# Audio-Beamformer_LED_V1_0.net
KiCad netlist of a schematic drawn in Altium Designer
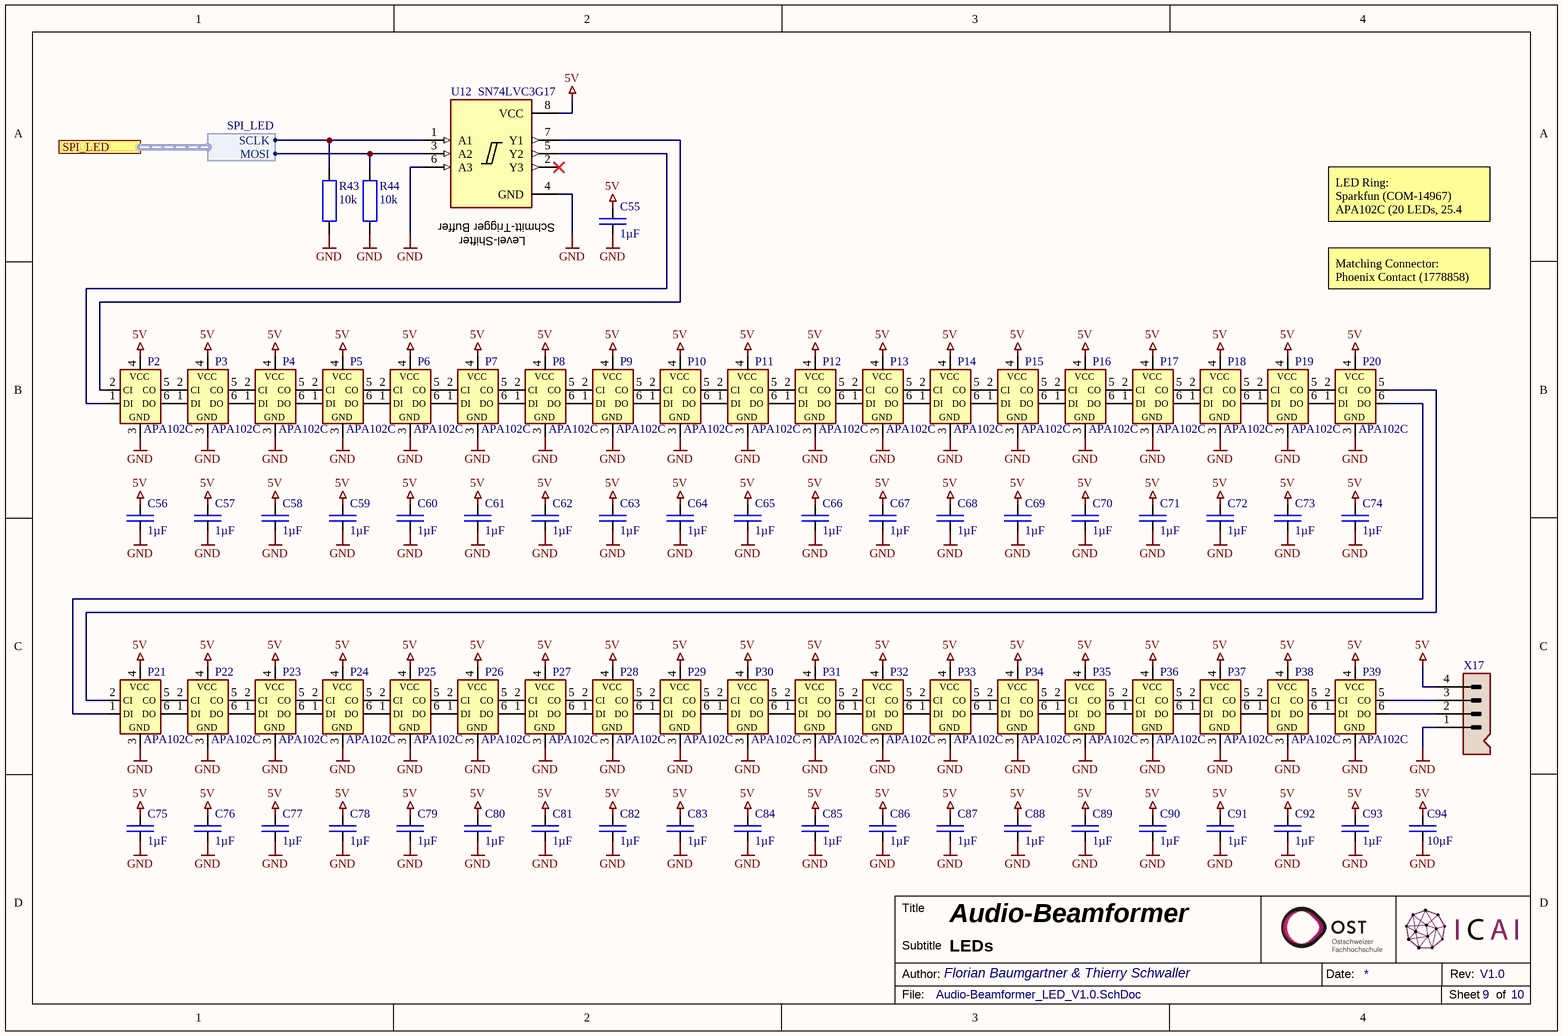
[diagram p0: Audio-Beamformer_LED_V1.0.SchDoc]

(export (version "E")
  (design (tool "Eeschema 10.0.6"))
  (components
    (comp (ref "C55")
      (value "1µF")
      (footprint "SMD Keramikkondensator 0603")
      (description "CAP-MK")
      (libsource (lib "AudioAmp") (part "C-CAPACITOR"))
    )
    (comp (ref "C56")
      (value "1µF")
      (footprint "SMD Keramikkondensator 0603")
      (description "CAP-MK")
      (libsource (lib "AudioAmp") (part "C-CAPACITOR"))
    )
    (comp (ref "C57")
      (value "1µF")
      (footprint "SMD Keramikkondensator 0603")
      (description "CAP-MK")
      (libsource (lib "AudioAmp") (part "C-CAPACITOR"))
    )
    (comp (ref "C58")
      (value "1µF")
      (footprint "SMD Keramikkondensator 0603")
      (description "CAP-MK")
      (libsource (lib "AudioAmp") (part "C-CAPACITOR"))
    )
    (comp (ref "C59")
      (value "1µF")
      (footprint "SMD Keramikkondensator 0603")
      (description "CAP-MK")
      (libsource (lib "AudioAmp") (part "C-CAPACITOR"))
    )
    (comp (ref "C60")
      (value "1µF")
      (footprint "SMD Keramikkondensator 0603")
      (description "CAP-MK")
      (libsource (lib "AudioAmp") (part "C-CAPACITOR"))
    )
    (comp (ref "C61")
      (value "1µF")
      (footprint "SMD Keramikkondensator 0603")
      (description "CAP-MK")
      (libsource (lib "AudioAmp") (part "C-CAPACITOR"))
    )
    (comp (ref "C62")
      (value "1µF")
      (footprint "SMD Keramikkondensator 0603")
      (description "CAP-MK")
      (libsource (lib "AudioAmp") (part "C-CAPACITOR"))
    )
    (comp (ref "C63")
      (value "1µF")
      (footprint "SMD Keramikkondensator 0603")
      (description "CAP-MK")
      (libsource (lib "AudioAmp") (part "C-CAPACITOR"))
    )
    (comp (ref "C64")
      (value "1µF")
      (footprint "SMD Keramikkondensator 0603")
      (description "CAP-MK")
      (libsource (lib "AudioAmp") (part "C-CAPACITOR"))
    )
    (comp (ref "C65")
      (value "1µF")
      (footprint "SMD Keramikkondensator 0603")
      (description "CAP-MK")
      (libsource (lib "AudioAmp") (part "C-CAPACITOR"))
    )
    (comp (ref "C66")
      (value "1µF")
      (footprint "SMD Keramikkondensator 0603")
      (description "CAP-MK")
      (libsource (lib "AudioAmp") (part "C-CAPACITOR"))
    )
    (comp (ref "C67")
      (value "1µF")
      (footprint "SMD Keramikkondensator 0603")
      (description "CAP-MK")
      (libsource (lib "AudioAmp") (part "C-CAPACITOR"))
    )
    (comp (ref "C68")
      (value "1µF")
      (footprint "SMD Keramikkondensator 0603")
      (description "CAP-MK")
      (libsource (lib "AudioAmp") (part "C-CAPACITOR"))
    )
    (comp (ref "C69")
      (value "1µF")
      (footprint "SMD Keramikkondensator 0603")
      (description "CAP-MK")
      (libsource (lib "AudioAmp") (part "C-CAPACITOR"))
    )
    (comp (ref "C70")
      (value "1µF")
      (footprint "SMD Keramikkondensator 0603")
      (description "CAP-MK")
      (libsource (lib "AudioAmp") (part "C-CAPACITOR"))
    )
    (comp (ref "C71")
      (value "1µF")
      (footprint "SMD Keramikkondensator 0603")
      (description "CAP-MK")
      (libsource (lib "AudioAmp") (part "C-CAPACITOR"))
    )
    (comp (ref "C72")
      (value "1µF")
      (footprint "SMD Keramikkondensator 0603")
      (description "CAP-MK")
      (libsource (lib "AudioAmp") (part "C-CAPACITOR"))
    )
    (comp (ref "C73")
      (value "1µF")
      (footprint "SMD Keramikkondensator 0603")
      (description "CAP-MK")
      (libsource (lib "AudioAmp") (part "C-CAPACITOR"))
    )
    (comp (ref "C74")
      (value "1µF")
      (footprint "SMD Keramikkondensator 0603")
      (description "CAP-MK")
      (libsource (lib "AudioAmp") (part "C-CAPACITOR"))
    )
    (comp (ref "C75")
      (value "1µF")
      (footprint "SMD Keramikkondensator 0603")
      (description "CAP-MK")
      (libsource (lib "AudioAmp") (part "C-CAPACITOR"))
    )
    (comp (ref "C76")
      (value "1µF")
      (footprint "SMD Keramikkondensator 0603")
      (description "CAP-MK")
      (libsource (lib "AudioAmp") (part "C-CAPACITOR"))
    )
    (comp (ref "C77")
      (value "1µF")
      (footprint "SMD Keramikkondensator 0603")
      (description "CAP-MK")
      (libsource (lib "AudioAmp") (part "C-CAPACITOR"))
    )
    (comp (ref "C78")
      (value "1µF")
      (footprint "SMD Keramikkondensator 0603")
      (description "CAP-MK")
      (libsource (lib "AudioAmp") (part "C-CAPACITOR"))
    )
    (comp (ref "C79")
      (value "1µF")
      (footprint "SMD Keramikkondensator 0603")
      (description "CAP-MK")
      (libsource (lib "AudioAmp") (part "C-CAPACITOR"))
    )
    (comp (ref "C80")
      (value "1µF")
      (footprint "SMD Keramikkondensator 0603")
      (description "CAP-MK")
      (libsource (lib "AudioAmp") (part "C-CAPACITOR"))
    )
    (comp (ref "C81")
      (value "1µF")
      (footprint "SMD Keramikkondensator 0603")
      (description "CAP-MK")
      (libsource (lib "AudioAmp") (part "C-CAPACITOR"))
    )
    (comp (ref "C82")
      (value "1µF")
      (footprint "SMD Keramikkondensator 0603")
      (description "CAP-MK")
      (libsource (lib "AudioAmp") (part "C-CAPACITOR"))
    )
    (comp (ref "C83")
      (value "1µF")
      (footprint "SMD Keramikkondensator 0603")
      (description "CAP-MK")
      (libsource (lib "AudioAmp") (part "C-CAPACITOR"))
    )
    (comp (ref "C84")
      (value "1µF")
      (footprint "SMD Keramikkondensator 0603")
      (description "CAP-MK")
      (libsource (lib "AudioAmp") (part "C-CAPACITOR"))
    )
    (comp (ref "C85")
      (value "1µF")
      (footprint "SMD Keramikkondensator 0603")
      (description "CAP-MK")
      (libsource (lib "AudioAmp") (part "C-CAPACITOR"))
    )
    (comp (ref "C86")
      (value "1µF")
      (footprint "SMD Keramikkondensator 0603")
      (description "CAP-MK")
      (libsource (lib "AudioAmp") (part "C-CAPACITOR"))
    )
    (comp (ref "C87")
      (value "1µF")
      (footprint "SMD Keramikkondensator 0603")
      (description "CAP-MK")
      (libsource (lib "AudioAmp") (part "C-CAPACITOR"))
    )
    (comp (ref "C88")
      (value "1µF")
      (footprint "SMD Keramikkondensator 0603")
      (description "CAP-MK")
      (libsource (lib "AudioAmp") (part "C-CAPACITOR"))
    )
    (comp (ref "C89")
      (value "1µF")
      (footprint "SMD Keramikkondensator 0603")
      (description "CAP-MK")
      (libsource (lib "AudioAmp") (part "C-CAPACITOR"))
    )
    (comp (ref "C90")
      (value "1µF")
      (footprint "SMD Keramikkondensator 0603")
      (description "CAP-MK")
      (libsource (lib "AudioAmp") (part "C-CAPACITOR"))
    )
    (comp (ref "C91")
      (value "1µF")
      (footprint "SMD Keramikkondensator 0603")
      (description "CAP-MK")
      (libsource (lib "AudioAmp") (part "C-CAPACITOR"))
    )
    (comp (ref "C92")
      (value "1µF")
      (footprint "SMD Keramikkondensator 0603")
      (description "CAP-MK")
      (libsource (lib "AudioAmp") (part "C-CAPACITOR"))
    )
    (comp (ref "C93")
      (value "1µF")
      (footprint "SMD Keramikkondensator 0603")
      (description "CAP-MK")
      (libsource (lib "AudioAmp") (part "C-CAPACITOR"))
    )
    (comp (ref "C94")
      (value "10µF")
      (footprint "SMD Keramikkondensator 1206")
      (description "CAP-MK")
      (libsource (lib "AudioAmp") (part "C-CAPACITOR"))
    )
    (comp (ref "P2")
      (value "APA102C")
      (footprint "SMD LED APA102C-5050")
      (description "Smart RGB-LED")
      (libsource (lib "Audio-Beamformer") (part "P-APA102C"))
    )
    (comp (ref "P3")
      (value "APA102C")
      (footprint "SMD LED APA102C-5050")
      (description "Smart RGB-LED")
      (libsource (lib "Audio-Beamformer") (part "P-APA102C"))
    )
    (comp (ref "P4")
      (value "APA102C")
      (footprint "SMD LED APA102C-5050")
      (description "Smart RGB-LED")
      (libsource (lib "Audio-Beamformer") (part "P-APA102C"))
    )
    (comp (ref "P5")
      (value "APA102C")
      (footprint "SMD LED APA102C-5050")
      (description "Smart RGB-LED")
      (libsource (lib "Audio-Beamformer") (part "P-APA102C"))
    )
    (comp (ref "P6")
      (value "APA102C")
      (footprint "SMD LED APA102C-5050")
      (description "Smart RGB-LED")
      (libsource (lib "Audio-Beamformer") (part "P-APA102C"))
    )
    (comp (ref "P7")
      (value "APA102C")
      (footprint "SMD LED APA102C-5050")
      (description "Smart RGB-LED")
      (libsource (lib "Audio-Beamformer") (part "P-APA102C"))
    )
    (comp (ref "P8")
      (value "APA102C")
      (footprint "SMD LED APA102C-5050")
      (description "Smart RGB-LED")
      (libsource (lib "Audio-Beamformer") (part "P-APA102C"))
    )
    (comp (ref "P9")
      (value "APA102C")
      (footprint "SMD LED APA102C-5050")
      (description "Smart RGB-LED")
      (libsource (lib "Audio-Beamformer") (part "P-APA102C"))
    )
    (comp (ref "P10")
      (value "APA102C")
      (footprint "SMD LED APA102C-5050")
      (description "Smart RGB-LED")
      (libsource (lib "Audio-Beamformer") (part "P-APA102C"))
    )
    (comp (ref "P11")
      (value "APA102C")
      (footprint "SMD LED APA102C-5050")
      (description "Smart RGB-LED")
      (libsource (lib "Audio-Beamformer") (part "P-APA102C"))
    )
    (comp (ref "P12")
      (value "APA102C")
      (footprint "SMD LED APA102C-5050")
      (description "Smart RGB-LED")
      (libsource (lib "Audio-Beamformer") (part "P-APA102C"))
    )
    (comp (ref "P13")
      (value "APA102C")
      (footprint "SMD LED APA102C-5050")
      (description "Smart RGB-LED")
      (libsource (lib "Audio-Beamformer") (part "P-APA102C"))
    )
    (comp (ref "P14")
      (value "APA102C")
      (footprint "SMD LED APA102C-5050")
      (description "Smart RGB-LED")
      (libsource (lib "Audio-Beamformer") (part "P-APA102C"))
    )
    (comp (ref "P15")
      (value "APA102C")
      (footprint "SMD LED APA102C-5050")
      (description "Smart RGB-LED")
      (libsource (lib "Audio-Beamformer") (part "P-APA102C"))
    )
    (comp (ref "P16")
      (value "APA102C")
      (footprint "SMD LED APA102C-5050")
      (description "Smart RGB-LED")
      (libsource (lib "Audio-Beamformer") (part "P-APA102C"))
    )
    (comp (ref "P17")
      (value "APA102C")
      (footprint "SMD LED APA102C-5050")
      (description "Smart RGB-LED")
      (libsource (lib "Audio-Beamformer") (part "P-APA102C"))
    )
    (comp (ref "P18")
      (value "APA102C")
      (footprint "SMD LED APA102C-5050")
      (description "Smart RGB-LED")
      (libsource (lib "Audio-Beamformer") (part "P-APA102C"))
    )
    (comp (ref "P19")
      (value "APA102C")
      (footprint "SMD LED APA102C-5050")
      (description "Smart RGB-LED")
      (libsource (lib "Audio-Beamformer") (part "P-APA102C"))
    )
    (comp (ref "P20")
      (value "APA102C")
      (footprint "SMD LED APA102C-5050")
      (description "Smart RGB-LED")
      (libsource (lib "Audio-Beamformer") (part "P-APA102C"))
    )
    (comp (ref "P21")
      (value "APA102C")
      (footprint "SMD LED APA102C-5050")
      (description "Smart RGB-LED")
      (libsource (lib "Audio-Beamformer") (part "P-APA102C"))
    )
    (comp (ref "P22")
      (value "APA102C")
      (footprint "SMD LED APA102C-5050")
      (description "Smart RGB-LED")
      (libsource (lib "Audio-Beamformer") (part "P-APA102C"))
    )
    (comp (ref "P23")
      (value "APA102C")
      (footprint "SMD LED APA102C-5050")
      (description "Smart RGB-LED")
      (libsource (lib "Audio-Beamformer") (part "P-APA102C"))
    )
    (comp (ref "P24")
      (value "APA102C")
      (footprint "SMD LED APA102C-5050")
      (description "Smart RGB-LED")
      (libsource (lib "Audio-Beamformer") (part "P-APA102C"))
    )
    (comp (ref "P25")
      (value "APA102C")
      (footprint "SMD LED APA102C-5050")
      (description "Smart RGB-LED")
      (libsource (lib "Audio-Beamformer") (part "P-APA102C"))
    )
    (comp (ref "P26")
      (value "APA102C")
      (footprint "SMD LED APA102C-5050")
      (description "Smart RGB-LED")
      (libsource (lib "Audio-Beamformer") (part "P-APA102C"))
    )
    (comp (ref "P27")
      (value "APA102C")
      (footprint "SMD LED APA102C-5050")
      (description "Smart RGB-LED")
      (libsource (lib "Audio-Beamformer") (part "P-APA102C"))
    )
    (comp (ref "P28")
      (value "APA102C")
      (footprint "SMD LED APA102C-5050")
      (description "Smart RGB-LED")
      (libsource (lib "Audio-Beamformer") (part "P-APA102C"))
    )
    (comp (ref "P29")
      (value "APA102C")
      (footprint "SMD LED APA102C-5050")
      (description "Smart RGB-LED")
      (libsource (lib "Audio-Beamformer") (part "P-APA102C"))
    )
    (comp (ref "P30")
      (value "APA102C")
      (footprint "SMD LED APA102C-5050")
      (description "Smart RGB-LED")
      (libsource (lib "Audio-Beamformer") (part "P-APA102C"))
    )
    (comp (ref "P31")
      (value "APA102C")
      (footprint "SMD LED APA102C-5050")
      (description "Smart RGB-LED")
      (libsource (lib "Audio-Beamformer") (part "P-APA102C"))
    )
    (comp (ref "P32")
      (value "APA102C")
      (footprint "SMD LED APA102C-5050")
      (description "Smart RGB-LED")
      (libsource (lib "Audio-Beamformer") (part "P-APA102C"))
    )
    (comp (ref "P33")
      (value "APA102C")
      (footprint "SMD LED APA102C-5050")
      (description "Smart RGB-LED")
      (libsource (lib "Audio-Beamformer") (part "P-APA102C"))
    )
    (comp (ref "P34")
      (value "APA102C")
      (footprint "SMD LED APA102C-5050")
      (description "Smart RGB-LED")
      (libsource (lib "Audio-Beamformer") (part "P-APA102C"))
    )
    (comp (ref "P35")
      (value "APA102C")
      (footprint "SMD LED APA102C-5050")
      (description "Smart RGB-LED")
      (libsource (lib "Audio-Beamformer") (part "P-APA102C"))
    )
    (comp (ref "P36")
      (value "APA102C")
      (footprint "SMD LED APA102C-5050")
      (description "Smart RGB-LED")
      (libsource (lib "Audio-Beamformer") (part "P-APA102C"))
    )
    (comp (ref "P37")
      (value "APA102C")
      (footprint "SMD LED APA102C-5050")
      (description "Smart RGB-LED")
      (libsource (lib "Audio-Beamformer") (part "P-APA102C"))
    )
    (comp (ref "P38")
      (value "APA102C")
      (footprint "SMD LED APA102C-5050")
      (description "Smart RGB-LED")
      (libsource (lib "Audio-Beamformer") (part "P-APA102C"))
    )
    (comp (ref "P39")
      (value "APA102C")
      (footprint "SMD LED APA102C-5050")
      (description "Smart RGB-LED")
      (libsource (lib "Audio-Beamformer") (part "P-APA102C"))
    )
    (comp (ref "R43")
      (value "10k")
      (footprint "SMD Widerstand 0603")
      (description "RES (E=Heizwiderstand B=Messwandler)")
      (libsource (lib "TFS Integrated Library") (part "R-RESISTOR"))
    )
    (comp (ref "R44")
      (value "10k")
      (footprint "SMD Widerstand 0603")
      (description "RES (E=Heizwiderstand B=Messwandler)")
      (libsource (lib "TFS Integrated Library") (part "R-RESISTOR"))
    )
    (comp (ref "U12")
      (value "SN74LVC3G17")
      (footprint "SMD IC SM-8")
      (description "Tripple Schmitt-Trigger Buffer")
      (libsource (lib "Audio-Beamformer") (part "U-SN74LVC3G17DCTR"))
    )
    (comp (ref "X17")
      (value "Board-To-Wire Connector (Receptacle)")
      (footprint "THT Connector 2.5mm 4-Pol (1778641)")
      (libsource (lib "Audio-Beamformer") (part "X-Stiftleiste (4-Fach)"))
    )
  )
  (nets
    (net (code "3") (name "5V") (class "Default")
      (node (ref "C55") (pin "2") (pinfunction "2_2") (pintype "passive"))
      (node (ref "C56") (pin "2") (pinfunction "2_2") (pintype "passive"))
      (node (ref "C57") (pin "2") (pinfunction "2_2") (pintype "passive"))
      (node (ref "C58") (pin "2") (pinfunction "2_2") (pintype "passive"))
      (node (ref "C59") (pin "2") (pinfunction "2_2") (pintype "passive"))
      (node (ref "C60") (pin "2") (pinfunction "2_2") (pintype "passive"))
      (node (ref "C61") (pin "2") (pinfunction "2_2") (pintype "passive"))
      (node (ref "C62") (pin "2") (pinfunction "2_2") (pintype "passive"))
      (node (ref "C63") (pin "2") (pinfunction "2_2") (pintype "passive"))
      (node (ref "C64") (pin "2") (pinfunction "2_2") (pintype "passive"))
      (node (ref "C65") (pin "2") (pinfunction "2_2") (pintype "passive"))
      (node (ref "C66") (pin "2") (pinfunction "2_2") (pintype "passive"))
      (node (ref "C67") (pin "2") (pinfunction "2_2") (pintype "passive"))
      (node (ref "C68") (pin "2") (pinfunction "2_2") (pintype "passive"))
      (node (ref "C69") (pin "2") (pinfunction "2_2") (pintype "passive"))
      (node (ref "C70") (pin "2") (pinfunction "2_2") (pintype "passive"))
      (node (ref "C71") (pin "2") (pinfunction "2_2") (pintype "passive"))
      (node (ref "C72") (pin "2") (pinfunction "2_2") (pintype "passive"))
      (node (ref "C73") (pin "2") (pinfunction "2_2") (pintype "passive"))
      (node (ref "C74") (pin "2") (pinfunction "2_2") (pintype "passive"))
      (node (ref "C75") (pin "2") (pinfunction "2_2") (pintype "passive"))
      (node (ref "C76") (pin "2") (pinfunction "2_2") (pintype "passive"))
      (node (ref "C77") (pin "2") (pinfunction "2_2") (pintype "passive"))
      (node (ref "C78") (pin "2") (pinfunction "2_2") (pintype "passive"))
      (node (ref "C79") (pin "2") (pinfunction "2_2") (pintype "passive"))
      (node (ref "C80") (pin "2") (pinfunction "2_2") (pintype "passive"))
      (node (ref "C81") (pin "2") (pinfunction "2_2") (pintype "passive"))
      (node (ref "C82") (pin "2") (pinfunction "2_2") (pintype "passive"))
      (node (ref "C83") (pin "2") (pinfunction "2_2") (pintype "passive"))
      (node (ref "C84") (pin "2") (pinfunction "2_2") (pintype "passive"))
      (node (ref "C85") (pin "2") (pinfunction "2_2") (pintype "passive"))
      (node (ref "C86") (pin "2") (pinfunction "2_2") (pintype "passive"))
      (node (ref "C87") (pin "2") (pinfunction "2_2") (pintype "passive"))
      (node (ref "C88") (pin "2") (pinfunction "2_2") (pintype "passive"))
      (node (ref "C89") (pin "2") (pinfunction "2_2") (pintype "passive"))
      (node (ref "C90") (pin "2") (pinfunction "2_2") (pintype "passive"))
      (node (ref "C91") (pin "2") (pinfunction "2_2") (pintype "passive"))
      (node (ref "C92") (pin "2") (pinfunction "2_2") (pintype "passive"))
      (node (ref "C93") (pin "2") (pinfunction "2_2") (pintype "passive"))
      (node (ref "C94") (pin "2") (pinfunction "2_2") (pintype "passive"))
      (node (ref "P10") (pin "4") (pinfunction "VCC_4") (pintype "power_in"))
      (node (ref "P11") (pin "4") (pinfunction "VCC_4") (pintype "power_in"))
      (node (ref "P12") (pin "4") (pinfunction "VCC_4") (pintype "power_in"))
      (node (ref "P13") (pin "4") (pinfunction "VCC_4") (pintype "power_in"))
      (node (ref "P14") (pin "4") (pinfunction "VCC_4") (pintype "power_in"))
      (node (ref "P15") (pin "4") (pinfunction "VCC_4") (pintype "power_in"))
      (node (ref "P16") (pin "4") (pinfunction "VCC_4") (pintype "power_in"))
      (node (ref "P17") (pin "4") (pinfunction "VCC_4") (pintype "power_in"))
      (node (ref "P18") (pin "4") (pinfunction "VCC_4") (pintype "power_in"))
      (node (ref "P19") (pin "4") (pinfunction "VCC_4") (pintype "power_in"))
      (node (ref "P2") (pin "4") (pinfunction "VCC_4") (pintype "power_in"))
      (node (ref "P20") (pin "4") (pinfunction "VCC_4") (pintype "power_in"))
      (node (ref "P21") (pin "4") (pinfunction "VCC_4") (pintype "power_in"))
      (node (ref "P22") (pin "4") (pinfunction "VCC_4") (pintype "power_in"))
      (node (ref "P23") (pin "4") (pinfunction "VCC_4") (pintype "power_in"))
      (node (ref "P24") (pin "4") (pinfunction "VCC_4") (pintype "power_in"))
      (node (ref "P25") (pin "4") (pinfunction "VCC_4") (pintype "power_in"))
      (node (ref "P26") (pin "4") (pinfunction "VCC_4") (pintype "power_in"))
      (node (ref "P27") (pin "4") (pinfunction "VCC_4") (pintype "power_in"))
      (node (ref "P28") (pin "4") (pinfunction "VCC_4") (pintype "power_in"))
      (node (ref "P29") (pin "4") (pinfunction "VCC_4") (pintype "power_in"))
      (node (ref "P3") (pin "4") (pinfunction "VCC_4") (pintype "power_in"))
      (node (ref "P30") (pin "4") (pinfunction "VCC_4") (pintype "power_in"))
      (node (ref "P31") (pin "4") (pinfunction "VCC_4") (pintype "power_in"))
      (node (ref "P32") (pin "4") (pinfunction "VCC_4") (pintype "power_in"))
      (node (ref "P33") (pin "4") (pinfunction "VCC_4") (pintype "power_in"))
      (node (ref "P34") (pin "4") (pinfunction "VCC_4") (pintype "power_in"))
      (node (ref "P35") (pin "4") (pinfunction "VCC_4") (pintype "power_in"))
      (node (ref "P36") (pin "4") (pinfunction "VCC_4") (pintype "power_in"))
      (node (ref "P37") (pin "4") (pinfunction "VCC_4") (pintype "power_in"))
      (node (ref "P38") (pin "4") (pinfunction "VCC_4") (pintype "power_in"))
      (node (ref "P39") (pin "4") (pinfunction "VCC_4") (pintype "power_in"))
      (node (ref "P4") (pin "4") (pinfunction "VCC_4") (pintype "power_in"))
      (node (ref "P5") (pin "4") (pinfunction "VCC_4") (pintype "power_in"))
      (node (ref "P6") (pin "4") (pinfunction "VCC_4") (pintype "power_in"))
      (node (ref "P7") (pin "4") (pinfunction "VCC_4") (pintype "power_in"))
      (node (ref "P8") (pin "4") (pinfunction "VCC_4") (pintype "power_in"))
      (node (ref "P9") (pin "4") (pinfunction "VCC_4") (pintype "power_in"))
      (node (ref "U12") (pin "8") (pinfunction "VCC_8") (pintype "power_in"))
      (node (ref "X17") (pin "4") (pinfunction "4_4") (pintype "passive"))
    )
    (net (code "4") (name "GND") (class "Default")
      (node (ref "C55") (pin "1") (pinfunction "1_1") (pintype "passive"))
      (node (ref "C56") (pin "1") (pinfunction "1_1") (pintype "passive"))
      (node (ref "C57") (pin "1") (pinfunction "1_1") (pintype "passive"))
      (node (ref "C58") (pin "1") (pinfunction "1_1") (pintype "passive"))
      (node (ref "C59") (pin "1") (pinfunction "1_1") (pintype "passive"))
      (node (ref "C60") (pin "1") (pinfunction "1_1") (pintype "passive"))
      (node (ref "C61") (pin "1") (pinfunction "1_1") (pintype "passive"))
      (node (ref "C62") (pin "1") (pinfunction "1_1") (pintype "passive"))
      (node (ref "C63") (pin "1") (pinfunction "1_1") (pintype "passive"))
      (node (ref "C64") (pin "1") (pinfunction "1_1") (pintype "passive"))
      (node (ref "C65") (pin "1") (pinfunction "1_1") (pintype "passive"))
      (node (ref "C66") (pin "1") (pinfunction "1_1") (pintype "passive"))
      (node (ref "C67") (pin "1") (pinfunction "1_1") (pintype "passive"))
      (node (ref "C68") (pin "1") (pinfunction "1_1") (pintype "passive"))
      (node (ref "C69") (pin "1") (pinfunction "1_1") (pintype "passive"))
      (node (ref "C70") (pin "1") (pinfunction "1_1") (pintype "passive"))
      (node (ref "C71") (pin "1") (pinfunction "1_1") (pintype "passive"))
      (node (ref "C72") (pin "1") (pinfunction "1_1") (pintype "passive"))
      (node (ref "C73") (pin "1") (pinfunction "1_1") (pintype "passive"))
      (node (ref "C74") (pin "1") (pinfunction "1_1") (pintype "passive"))
      (node (ref "C75") (pin "1") (pinfunction "1_1") (pintype "passive"))
      (node (ref "C76") (pin "1") (pinfunction "1_1") (pintype "passive"))
      (node (ref "C77") (pin "1") (pinfunction "1_1") (pintype "passive"))
      (node (ref "C78") (pin "1") (pinfunction "1_1") (pintype "passive"))
      (node (ref "C79") (pin "1") (pinfunction "1_1") (pintype "passive"))
      (node (ref "C80") (pin "1") (pinfunction "1_1") (pintype "passive"))
      (node (ref "C81") (pin "1") (pinfunction "1_1") (pintype "passive"))
      (node (ref "C82") (pin "1") (pinfunction "1_1") (pintype "passive"))
      (node (ref "C83") (pin "1") (pinfunction "1_1") (pintype "passive"))
      (node (ref "C84") (pin "1") (pinfunction "1_1") (pintype "passive"))
      (node (ref "C85") (pin "1") (pinfunction "1_1") (pintype "passive"))
      (node (ref "C86") (pin "1") (pinfunction "1_1") (pintype "passive"))
      (node (ref "C87") (pin "1") (pinfunction "1_1") (pintype "passive"))
      (node (ref "C88") (pin "1") (pinfunction "1_1") (pintype "passive"))
      (node (ref "C89") (pin "1") (pinfunction "1_1") (pintype "passive"))
      (node (ref "C90") (pin "1") (pinfunction "1_1") (pintype "passive"))
      (node (ref "C91") (pin "1") (pinfunction "1_1") (pintype "passive"))
      (node (ref "C92") (pin "1") (pinfunction "1_1") (pintype "passive"))
      (node (ref "C93") (pin "1") (pinfunction "1_1") (pintype "passive"))
      (node (ref "C94") (pin "1") (pinfunction "1_1") (pintype "passive"))
      (node (ref "P10") (pin "3") (pinfunction "GND_3") (pintype "power_in"))
      (node (ref "P11") (pin "3") (pinfunction "GND_3") (pintype "power_in"))
      (node (ref "P12") (pin "3") (pinfunction "GND_3") (pintype "power_in"))
      (node (ref "P13") (pin "3") (pinfunction "GND_3") (pintype "power_in"))
      (node (ref "P14") (pin "3") (pinfunction "GND_3") (pintype "power_in"))
      (node (ref "P15") (pin "3") (pinfunction "GND_3") (pintype "power_in"))
      (node (ref "P16") (pin "3") (pinfunction "GND_3") (pintype "power_in"))
      (node (ref "P17") (pin "3") (pinfunction "GND_3") (pintype "power_in"))
      (node (ref "P18") (pin "3") (pinfunction "GND_3") (pintype "power_in"))
      (node (ref "P19") (pin "3") (pinfunction "GND_3") (pintype "power_in"))
      (node (ref "P2") (pin "3") (pinfunction "GND_3") (pintype "power_in"))
      (node (ref "P20") (pin "3") (pinfunction "GND_3") (pintype "power_in"))
      (node (ref "P21") (pin "3") (pinfunction "GND_3") (pintype "power_in"))
      (node (ref "P22") (pin "3") (pinfunction "GND_3") (pintype "power_in"))
      (node (ref "P23") (pin "3") (pinfunction "GND_3") (pintype "power_in"))
      (node (ref "P24") (pin "3") (pinfunction "GND_3") (pintype "power_in"))
      (node (ref "P25") (pin "3") (pinfunction "GND_3") (pintype "power_in"))
      (node (ref "P26") (pin "3") (pinfunction "GND_3") (pintype "power_in"))
      (node (ref "P27") (pin "3") (pinfunction "GND_3") (pintype "power_in"))
      (node (ref "P28") (pin "3") (pinfunction "GND_3") (pintype "power_in"))
      (node (ref "P29") (pin "3") (pinfunction "GND_3") (pintype "power_in"))
      (node (ref "P3") (pin "3") (pinfunction "GND_3") (pintype "power_in"))
      (node (ref "P30") (pin "3") (pinfunction "GND_3") (pintype "power_in"))
      (node (ref "P31") (pin "3") (pinfunction "GND_3") (pintype "power_in"))
      (node (ref "P32") (pin "3") (pinfunction "GND_3") (pintype "power_in"))
      (node (ref "P33") (pin "3") (pinfunction "GND_3") (pintype "power_in"))
      (node (ref "P34") (pin "3") (pinfunction "GND_3") (pintype "power_in"))
      (node (ref "P35") (pin "3") (pinfunction "GND_3") (pintype "power_in"))
      (node (ref "P36") (pin "3") (pinfunction "GND_3") (pintype "power_in"))
      (node (ref "P37") (pin "3") (pinfunction "GND_3") (pintype "power_in"))
      (node (ref "P38") (pin "3") (pinfunction "GND_3") (pintype "power_in"))
      (node (ref "P39") (pin "3") (pinfunction "GND_3") (pintype "power_in"))
      (node (ref "P4") (pin "3") (pinfunction "GND_3") (pintype "power_in"))
      (node (ref "P5") (pin "3") (pinfunction "GND_3") (pintype "power_in"))
      (node (ref "P6") (pin "3") (pinfunction "GND_3") (pintype "power_in"))
      (node (ref "P7") (pin "3") (pinfunction "GND_3") (pintype "power_in"))
      (node (ref "P8") (pin "3") (pinfunction "GND_3") (pintype "power_in"))
      (node (ref "P9") (pin "3") (pinfunction "GND_3") (pintype "power_in"))
      (node (ref "R43") (pin "1") (pinfunction "1_1") (pintype "passive"))
      (node (ref "R44") (pin "1") (pinfunction "1_1") (pintype "passive"))
      (node (ref "U12") (pin "4") (pinfunction "GND_4") (pintype "power_in"))
      (node (ref "U12") (pin "6") (pinfunction "A3_6") (pintype "input"))
      (node (ref "X17") (pin "1") (pinfunction "1_1") (pintype "passive"))
    )
    (net (code "5") (name "Net-(P2-CI)") (class "Default")
      (node (ref "P2") (pin "2") (pinfunction "CI_2") (pintype "passive"))
      (node (ref "U12") (pin "7") (pinfunction "Y1_7") (pintype "output"))
    )
    (net (code "6") (name "Net-(P2-CO)") (class "Default")
      (node (ref "P2") (pin "5") (pinfunction "CO_5") (pintype "passive"))
      (node (ref "P3") (pin "2") (pinfunction "CI_2") (pintype "passive"))
    )
    (net (code "7") (name "Net-(P2-DI)") (class "Default")
      (node (ref "P2") (pin "1") (pinfunction "DI_1") (pintype "passive"))
      (node (ref "U12") (pin "5") (pinfunction "Y2_5") (pintype "output"))
    )
    (net (code "8") (name "Net-(P2-DO)") (class "Default")
      (node (ref "P2") (pin "6") (pinfunction "DO_6") (pintype "passive"))
      (node (ref "P3") (pin "1") (pinfunction "DI_1") (pintype "passive"))
    )
    (net (code "9") (name "Net-(P3-CO)") (class "Default")
      (node (ref "P3") (pin "5") (pinfunction "CO_5") (pintype "passive"))
      (node (ref "P4") (pin "2") (pinfunction "CI_2") (pintype "passive"))
    )
    (net (code "10") (name "Net-(P3-DO)") (class "Default")
      (node (ref "P3") (pin "6") (pinfunction "DO_6") (pintype "passive"))
      (node (ref "P4") (pin "1") (pinfunction "DI_1") (pintype "passive"))
    )
    (net (code "11") (name "Net-(P4-CO)") (class "Default")
      (node (ref "P4") (pin "5") (pinfunction "CO_5") (pintype "passive"))
      (node (ref "P5") (pin "2") (pinfunction "CI_2") (pintype "passive"))
    )
    (net (code "12") (name "Net-(P4-DO)") (class "Default")
      (node (ref "P4") (pin "6") (pinfunction "DO_6") (pintype "passive"))
      (node (ref "P5") (pin "1") (pinfunction "DI_1") (pintype "passive"))
    )
    (net (code "13") (name "Net-(P5-CO)") (class "Default")
      (node (ref "P5") (pin "5") (pinfunction "CO_5") (pintype "passive"))
      (node (ref "P6") (pin "2") (pinfunction "CI_2") (pintype "passive"))
    )
    (net (code "14") (name "Net-(P5-DO)") (class "Default")
      (node (ref "P5") (pin "6") (pinfunction "DO_6") (pintype "passive"))
      (node (ref "P6") (pin "1") (pinfunction "DI_1") (pintype "passive"))
    )
    (net (code "15") (name "Net-(P6-CO)") (class "Default")
      (node (ref "P6") (pin "5") (pinfunction "CO_5") (pintype "passive"))
      (node (ref "P7") (pin "2") (pinfunction "CI_2") (pintype "passive"))
    )
    (net (code "16") (name "Net-(P6-DO)") (class "Default")
      (node (ref "P6") (pin "6") (pinfunction "DO_6") (pintype "passive"))
      (node (ref "P7") (pin "1") (pinfunction "DI_1") (pintype "passive"))
    )
    (net (code "17") (name "Net-(P7-CO)") (class "Default")
      (node (ref "P7") (pin "5") (pinfunction "CO_5") (pintype "passive"))
      (node (ref "P8") (pin "2") (pinfunction "CI_2") (pintype "passive"))
    )
    (net (code "18") (name "Net-(P7-DO)") (class "Default")
      (node (ref "P7") (pin "6") (pinfunction "DO_6") (pintype "passive"))
      (node (ref "P8") (pin "1") (pinfunction "DI_1") (pintype "passive"))
    )
    (net (code "19") (name "Net-(P8-CO)") (class "Default")
      (node (ref "P8") (pin "5") (pinfunction "CO_5") (pintype "passive"))
      (node (ref "P9") (pin "2") (pinfunction "CI_2") (pintype "passive"))
    )
    (net (code "20") (name "Net-(P8-DO)") (class "Default")
      (node (ref "P8") (pin "6") (pinfunction "DO_6") (pintype "passive"))
      (node (ref "P9") (pin "1") (pinfunction "DI_1") (pintype "passive"))
    )
    (net (code "21") (name "Net-(P10-CI)") (class "Default")
      (node (ref "P10") (pin "2") (pinfunction "CI_2") (pintype "passive"))
      (node (ref "P9") (pin "5") (pinfunction "CO_5") (pintype "passive"))
    )
    (net (code "22") (name "Net-(P10-CO)") (class "Default")
      (node (ref "P10") (pin "5") (pinfunction "CO_5") (pintype "passive"))
      (node (ref "P11") (pin "2") (pinfunction "CI_2") (pintype "passive"))
    )
    (net (code "23") (name "Net-(P10-DI)") (class "Default")
      (node (ref "P10") (pin "1") (pinfunction "DI_1") (pintype "passive"))
      (node (ref "P9") (pin "6") (pinfunction "DO_6") (pintype "passive"))
    )
    (net (code "24") (name "Net-(P10-DO)") (class "Default")
      (node (ref "P10") (pin "6") (pinfunction "DO_6") (pintype "passive"))
      (node (ref "P11") (pin "1") (pinfunction "DI_1") (pintype "passive"))
    )
    (net (code "25") (name "Net-(P11-CO)") (class "Default")
      (node (ref "P11") (pin "5") (pinfunction "CO_5") (pintype "passive"))
      (node (ref "P12") (pin "2") (pinfunction "CI_2") (pintype "passive"))
    )
    (net (code "26") (name "Net-(P11-DO)") (class "Default")
      (node (ref "P11") (pin "6") (pinfunction "DO_6") (pintype "passive"))
      (node (ref "P12") (pin "1") (pinfunction "DI_1") (pintype "passive"))
    )
    (net (code "27") (name "Net-(P12-CO)") (class "Default")
      (node (ref "P12") (pin "5") (pinfunction "CO_5") (pintype "passive"))
      (node (ref "P13") (pin "2") (pinfunction "CI_2") (pintype "passive"))
    )
    (net (code "28") (name "Net-(P12-DO)") (class "Default")
      (node (ref "P12") (pin "6") (pinfunction "DO_6") (pintype "passive"))
      (node (ref "P13") (pin "1") (pinfunction "DI_1") (pintype "passive"))
    )
    (net (code "29") (name "Net-(P13-CO)") (class "Default")
      (node (ref "P13") (pin "5") (pinfunction "CO_5") (pintype "passive"))
      (node (ref "P14") (pin "2") (pinfunction "CI_2") (pintype "passive"))
    )
    (net (code "30") (name "Net-(P13-DO)") (class "Default")
      (node (ref "P13") (pin "6") (pinfunction "DO_6") (pintype "passive"))
      (node (ref "P14") (pin "1") (pinfunction "DI_1") (pintype "passive"))
    )
    (net (code "31") (name "Net-(P14-CO)") (class "Default")
      (node (ref "P14") (pin "5") (pinfunction "CO_5") (pintype "passive"))
      (node (ref "P15") (pin "2") (pinfunction "CI_2") (pintype "passive"))
    )
    (net (code "32") (name "Net-(P14-DO)") (class "Default")
      (node (ref "P14") (pin "6") (pinfunction "DO_6") (pintype "passive"))
      (node (ref "P15") (pin "1") (pinfunction "DI_1") (pintype "passive"))
    )
    (net (code "33") (name "Net-(P15-CO)") (class "Default")
      (node (ref "P15") (pin "5") (pinfunction "CO_5") (pintype "passive"))
      (node (ref "P16") (pin "2") (pinfunction "CI_2") (pintype "passive"))
    )
    (net (code "34") (name "Net-(P15-DO)") (class "Default")
      (node (ref "P15") (pin "6") (pinfunction "DO_6") (pintype "passive"))
      (node (ref "P16") (pin "1") (pinfunction "DI_1") (pintype "passive"))
    )
    (net (code "35") (name "Net-(P16-CO)") (class "Default")
      (node (ref "P16") (pin "5") (pinfunction "CO_5") (pintype "passive"))
      (node (ref "P17") (pin "2") (pinfunction "CI_2") (pintype "passive"))
    )
    (net (code "36") (name "Net-(P16-DO)") (class "Default")
      (node (ref "P16") (pin "6") (pinfunction "DO_6") (pintype "passive"))
      (node (ref "P17") (pin "1") (pinfunction "DI_1") (pintype "passive"))
    )
    (net (code "37") (name "Net-(P17-CO)") (class "Default")
      (node (ref "P17") (pin "5") (pinfunction "CO_5") (pintype "passive"))
      (node (ref "P18") (pin "2") (pinfunction "CI_2") (pintype "passive"))
    )
    (net (code "38") (name "Net-(P17-DO)") (class "Default")
      (node (ref "P17") (pin "6") (pinfunction "DO_6") (pintype "passive"))
      (node (ref "P18") (pin "1") (pinfunction "DI_1") (pintype "passive"))
    )
    (net (code "39") (name "Net-(P18-CO)") (class "Default")
      (node (ref "P18") (pin "5") (pinfunction "CO_5") (pintype "passive"))
      (node (ref "P19") (pin "2") (pinfunction "CI_2") (pintype "passive"))
    )
    (net (code "40") (name "Net-(P18-DO)") (class "Default")
      (node (ref "P18") (pin "6") (pinfunction "DO_6") (pintype "passive"))
      (node (ref "P19") (pin "1") (pinfunction "DI_1") (pintype "passive"))
    )
    (net (code "41") (name "Net-(P19-CO)") (class "Default")
      (node (ref "P19") (pin "5") (pinfunction "CO_5") (pintype "passive"))
      (node (ref "P20") (pin "2") (pinfunction "CI_2") (pintype "passive"))
    )
    (net (code "42") (name "Net-(P19-DO)") (class "Default")
      (node (ref "P19") (pin "6") (pinfunction "DO_6") (pintype "passive"))
      (node (ref "P20") (pin "1") (pinfunction "DI_1") (pintype "passive"))
    )
    (net (code "43") (name "Net-(P20-CO)") (class "Default")
      (node (ref "P20") (pin "5") (pinfunction "CO_5") (pintype "passive"))
      (node (ref "P21") (pin "2") (pinfunction "CI_2") (pintype "passive"))
    )
    (net (code "44") (name "Net-(P20-DO)") (class "Default")
      (node (ref "P20") (pin "6") (pinfunction "DO_6") (pintype "passive"))
      (node (ref "P21") (pin "1") (pinfunction "DI_1") (pintype "passive"))
    )
    (net (code "45") (name "Net-(P21-CO)") (class "Default")
      (node (ref "P21") (pin "5") (pinfunction "CO_5") (pintype "passive"))
      (node (ref "P22") (pin "2") (pinfunction "CI_2") (pintype "passive"))
    )
    (net (code "46") (name "Net-(P21-DO)") (class "Default")
      (node (ref "P21") (pin "6") (pinfunction "DO_6") (pintype "passive"))
      (node (ref "P22") (pin "1") (pinfunction "DI_1") (pintype "passive"))
    )
    (net (code "47") (name "Net-(P22-CO)") (class "Default")
      (node (ref "P22") (pin "5") (pinfunction "CO_5") (pintype "passive"))
      (node (ref "P23") (pin "2") (pinfunction "CI_2") (pintype "passive"))
    )
    (net (code "48") (name "Net-(P22-DO)") (class "Default")
      (node (ref "P22") (pin "6") (pinfunction "DO_6") (pintype "passive"))
      (node (ref "P23") (pin "1") (pinfunction "DI_1") (pintype "passive"))
    )
    (net (code "49") (name "Net-(P23-CO)") (class "Default")
      (node (ref "P23") (pin "5") (pinfunction "CO_5") (pintype "passive"))
      (node (ref "P24") (pin "2") (pinfunction "CI_2") (pintype "passive"))
    )
    (net (code "50") (name "Net-(P23-DO)") (class "Default")
      (node (ref "P23") (pin "6") (pinfunction "DO_6") (pintype "passive"))
      (node (ref "P24") (pin "1") (pinfunction "DI_1") (pintype "passive"))
    )
    (net (code "51") (name "Net-(P24-CO)") (class "Default")
      (node (ref "P24") (pin "5") (pinfunction "CO_5") (pintype "passive"))
      (node (ref "P25") (pin "2") (pinfunction "CI_2") (pintype "passive"))
    )
    (net (code "52") (name "Net-(P24-DO)") (class "Default")
      (node (ref "P24") (pin "6") (pinfunction "DO_6") (pintype "passive"))
      (node (ref "P25") (pin "1") (pinfunction "DI_1") (pintype "passive"))
    )
    (net (code "53") (name "Net-(P25-CO)") (class "Default")
      (node (ref "P25") (pin "5") (pinfunction "CO_5") (pintype "passive"))
      (node (ref "P26") (pin "2") (pinfunction "CI_2") (pintype "passive"))
    )
    (net (code "54") (name "Net-(P25-DO)") (class "Default")
      (node (ref "P25") (pin "6") (pinfunction "DO_6") (pintype "passive"))
      (node (ref "P26") (pin "1") (pinfunction "DI_1") (pintype "passive"))
    )
    (net (code "55") (name "Net-(P26-CO)") (class "Default")
      (node (ref "P26") (pin "5") (pinfunction "CO_5") (pintype "passive"))
      (node (ref "P27") (pin "2") (pinfunction "CI_2") (pintype "passive"))
    )
    (net (code "56") (name "Net-(P26-DO)") (class "Default")
      (node (ref "P26") (pin "6") (pinfunction "DO_6") (pintype "passive"))
      (node (ref "P27") (pin "1") (pinfunction "DI_1") (pintype "passive"))
    )
    (net (code "57") (name "Net-(P27-CO)") (class "Default")
      (node (ref "P27") (pin "5") (pinfunction "CO_5") (pintype "passive"))
      (node (ref "P28") (pin "2") (pinfunction "CI_2") (pintype "passive"))
    )
    (net (code "58") (name "Net-(P27-DO)") (class "Default")
      (node (ref "P27") (pin "6") (pinfunction "DO_6") (pintype "passive"))
      (node (ref "P28") (pin "1") (pinfunction "DI_1") (pintype "passive"))
    )
    (net (code "59") (name "Net-(P28-CO)") (class "Default")
      (node (ref "P28") (pin "5") (pinfunction "CO_5") (pintype "passive"))
      (node (ref "P29") (pin "2") (pinfunction "CI_2") (pintype "passive"))
    )
    (net (code "60") (name "Net-(P28-DO)") (class "Default")
      (node (ref "P28") (pin "6") (pinfunction "DO_6") (pintype "passive"))
      (node (ref "P29") (pin "1") (pinfunction "DI_1") (pintype "passive"))
    )
    (net (code "61") (name "Net-(P29-CO)") (class "Default")
      (node (ref "P29") (pin "5") (pinfunction "CO_5") (pintype "passive"))
      (node (ref "P30") (pin "2") (pinfunction "CI_2") (pintype "passive"))
    )
    (net (code "62") (name "Net-(P29-DO)") (class "Default")
      (node (ref "P29") (pin "6") (pinfunction "DO_6") (pintype "passive"))
      (node (ref "P30") (pin "1") (pinfunction "DI_1") (pintype "passive"))
    )
    (net (code "63") (name "Net-(P30-CO)") (class "Default")
      (node (ref "P30") (pin "5") (pinfunction "CO_5") (pintype "passive"))
      (node (ref "P31") (pin "2") (pinfunction "CI_2") (pintype "passive"))
    )
    (net (code "64") (name "Net-(P30-DO)") (class "Default")
      (node (ref "P30") (pin "6") (pinfunction "DO_6") (pintype "passive"))
      (node (ref "P31") (pin "1") (pinfunction "DI_1") (pintype "passive"))
    )
    (net (code "65") (name "Net-(P31-CO)") (class "Default")
      (node (ref "P31") (pin "5") (pinfunction "CO_5") (pintype "passive"))
      (node (ref "P32") (pin "2") (pinfunction "CI_2") (pintype "passive"))
    )
    (net (code "66") (name "Net-(P31-DO)") (class "Default")
      (node (ref "P31") (pin "6") (pinfunction "DO_6") (pintype "passive"))
      (node (ref "P32") (pin "1") (pinfunction "DI_1") (pintype "passive"))
    )
    (net (code "67") (name "Net-(P32-CO)") (class "Default")
      (node (ref "P32") (pin "5") (pinfunction "CO_5") (pintype "passive"))
      (node (ref "P33") (pin "2") (pinfunction "CI_2") (pintype "passive"))
    )
    (net (code "68") (name "Net-(P32-DO)") (class "Default")
      (node (ref "P32") (pin "6") (pinfunction "DO_6") (pintype "passive"))
      (node (ref "P33") (pin "1") (pinfunction "DI_1") (pintype "passive"))
    )
    (net (code "69") (name "Net-(P33-CO)") (class "Default")
      (node (ref "P33") (pin "5") (pinfunction "CO_5") (pintype "passive"))
      (node (ref "P34") (pin "2") (pinfunction "CI_2") (pintype "passive"))
    )
    (net (code "70") (name "Net-(P33-DO)") (class "Default")
      (node (ref "P33") (pin "6") (pinfunction "DO_6") (pintype "passive"))
      (node (ref "P34") (pin "1") (pinfunction "DI_1") (pintype "passive"))
    )
    (net (code "71") (name "Net-(P34-CO)") (class "Default")
      (node (ref "P34") (pin "5") (pinfunction "CO_5") (pintype "passive"))
      (node (ref "P35") (pin "2") (pinfunction "CI_2") (pintype "passive"))
    )
    (net (code "72") (name "Net-(P34-DO)") (class "Default")
      (node (ref "P34") (pin "6") (pinfunction "DO_6") (pintype "passive"))
      (node (ref "P35") (pin "1") (pinfunction "DI_1") (pintype "passive"))
    )
    (net (code "73") (name "Net-(P35-CO)") (class "Default")
      (node (ref "P35") (pin "5") (pinfunction "CO_5") (pintype "passive"))
      (node (ref "P36") (pin "2") (pinfunction "CI_2") (pintype "passive"))
    )
    (net (code "74") (name "Net-(P35-DO)") (class "Default")
      (node (ref "P35") (pin "6") (pinfunction "DO_6") (pintype "passive"))
      (node (ref "P36") (pin "1") (pinfunction "DI_1") (pintype "passive"))
    )
    (net (code "75") (name "Net-(P36-CO)") (class "Default")
      (node (ref "P36") (pin "5") (pinfunction "CO_5") (pintype "passive"))
      (node (ref "P37") (pin "2") (pinfunction "CI_2") (pintype "passive"))
    )
    (net (code "76") (name "Net-(P36-DO)") (class "Default")
      (node (ref "P36") (pin "6") (pinfunction "DO_6") (pintype "passive"))
      (node (ref "P37") (pin "1") (pinfunction "DI_1") (pintype "passive"))
    )
    (net (code "77") (name "Net-(P37-CO)") (class "Default")
      (node (ref "P37") (pin "5") (pinfunction "CO_5") (pintype "passive"))
      (node (ref "P38") (pin "2") (pinfunction "CI_2") (pintype "passive"))
    )
    (net (code "78") (name "Net-(P37-DO)") (class "Default")
      (node (ref "P37") (pin "6") (pinfunction "DO_6") (pintype "passive"))
      (node (ref "P38") (pin "1") (pinfunction "DI_1") (pintype "passive"))
    )
    (net (code "79") (name "Net-(P38-CO)") (class "Default")
      (node (ref "P38") (pin "5") (pinfunction "CO_5") (pintype "passive"))
      (node (ref "P39") (pin "2") (pinfunction "CI_2") (pintype "passive"))
    )
    (net (code "80") (name "Net-(P38-DO)") (class "Default")
      (node (ref "P38") (pin "6") (pinfunction "DO_6") (pintype "passive"))
      (node (ref "P39") (pin "1") (pinfunction "DI_1") (pintype "passive"))
    )
    (net (code "81") (name "Net-(P39-CO)") (class "Default")
      (node (ref "P39") (pin "5") (pinfunction "CO_5") (pintype "passive"))
      (node (ref "X17") (pin "3") (pinfunction "3_3") (pintype "passive"))
    )
    (net (code "82") (name "Net-(P39-DO)") (class "Default")
      (node (ref "P39") (pin "6") (pinfunction "DO_6") (pintype "passive"))
      (node (ref "X17") (pin "2") (pinfunction "2_2") (pintype "passive"))
    )
    (net (code "83") (name "Net-(U12-A1)") (class "Default")
      (node (ref "R43") (pin "2") (pinfunction "2_2") (pintype "passive"))
      (node (ref "U12") (pin "1") (pinfunction "A1_1") (pintype "input"))
    )
    (net (code "84") (name "Net-(U12-A2)") (class "Default")
      (node (ref "R44") (pin "2") (pinfunction "2_2") (pintype "passive"))
      (node (ref "U12") (pin "3") (pinfunction "A2_3") (pintype "input"))
    )
    (net (code "85") (name "unconnected-(U12-Y3-Pad2)") (class "Default")
      (node (ref "U12") (pin "2") (pinfunction "Y3_2") (pintype "output+no_connect"))
    )
  )
)
